# ENTRENADOR_SMD.net
KiCad netlist of a schematic drawn in EAGLE
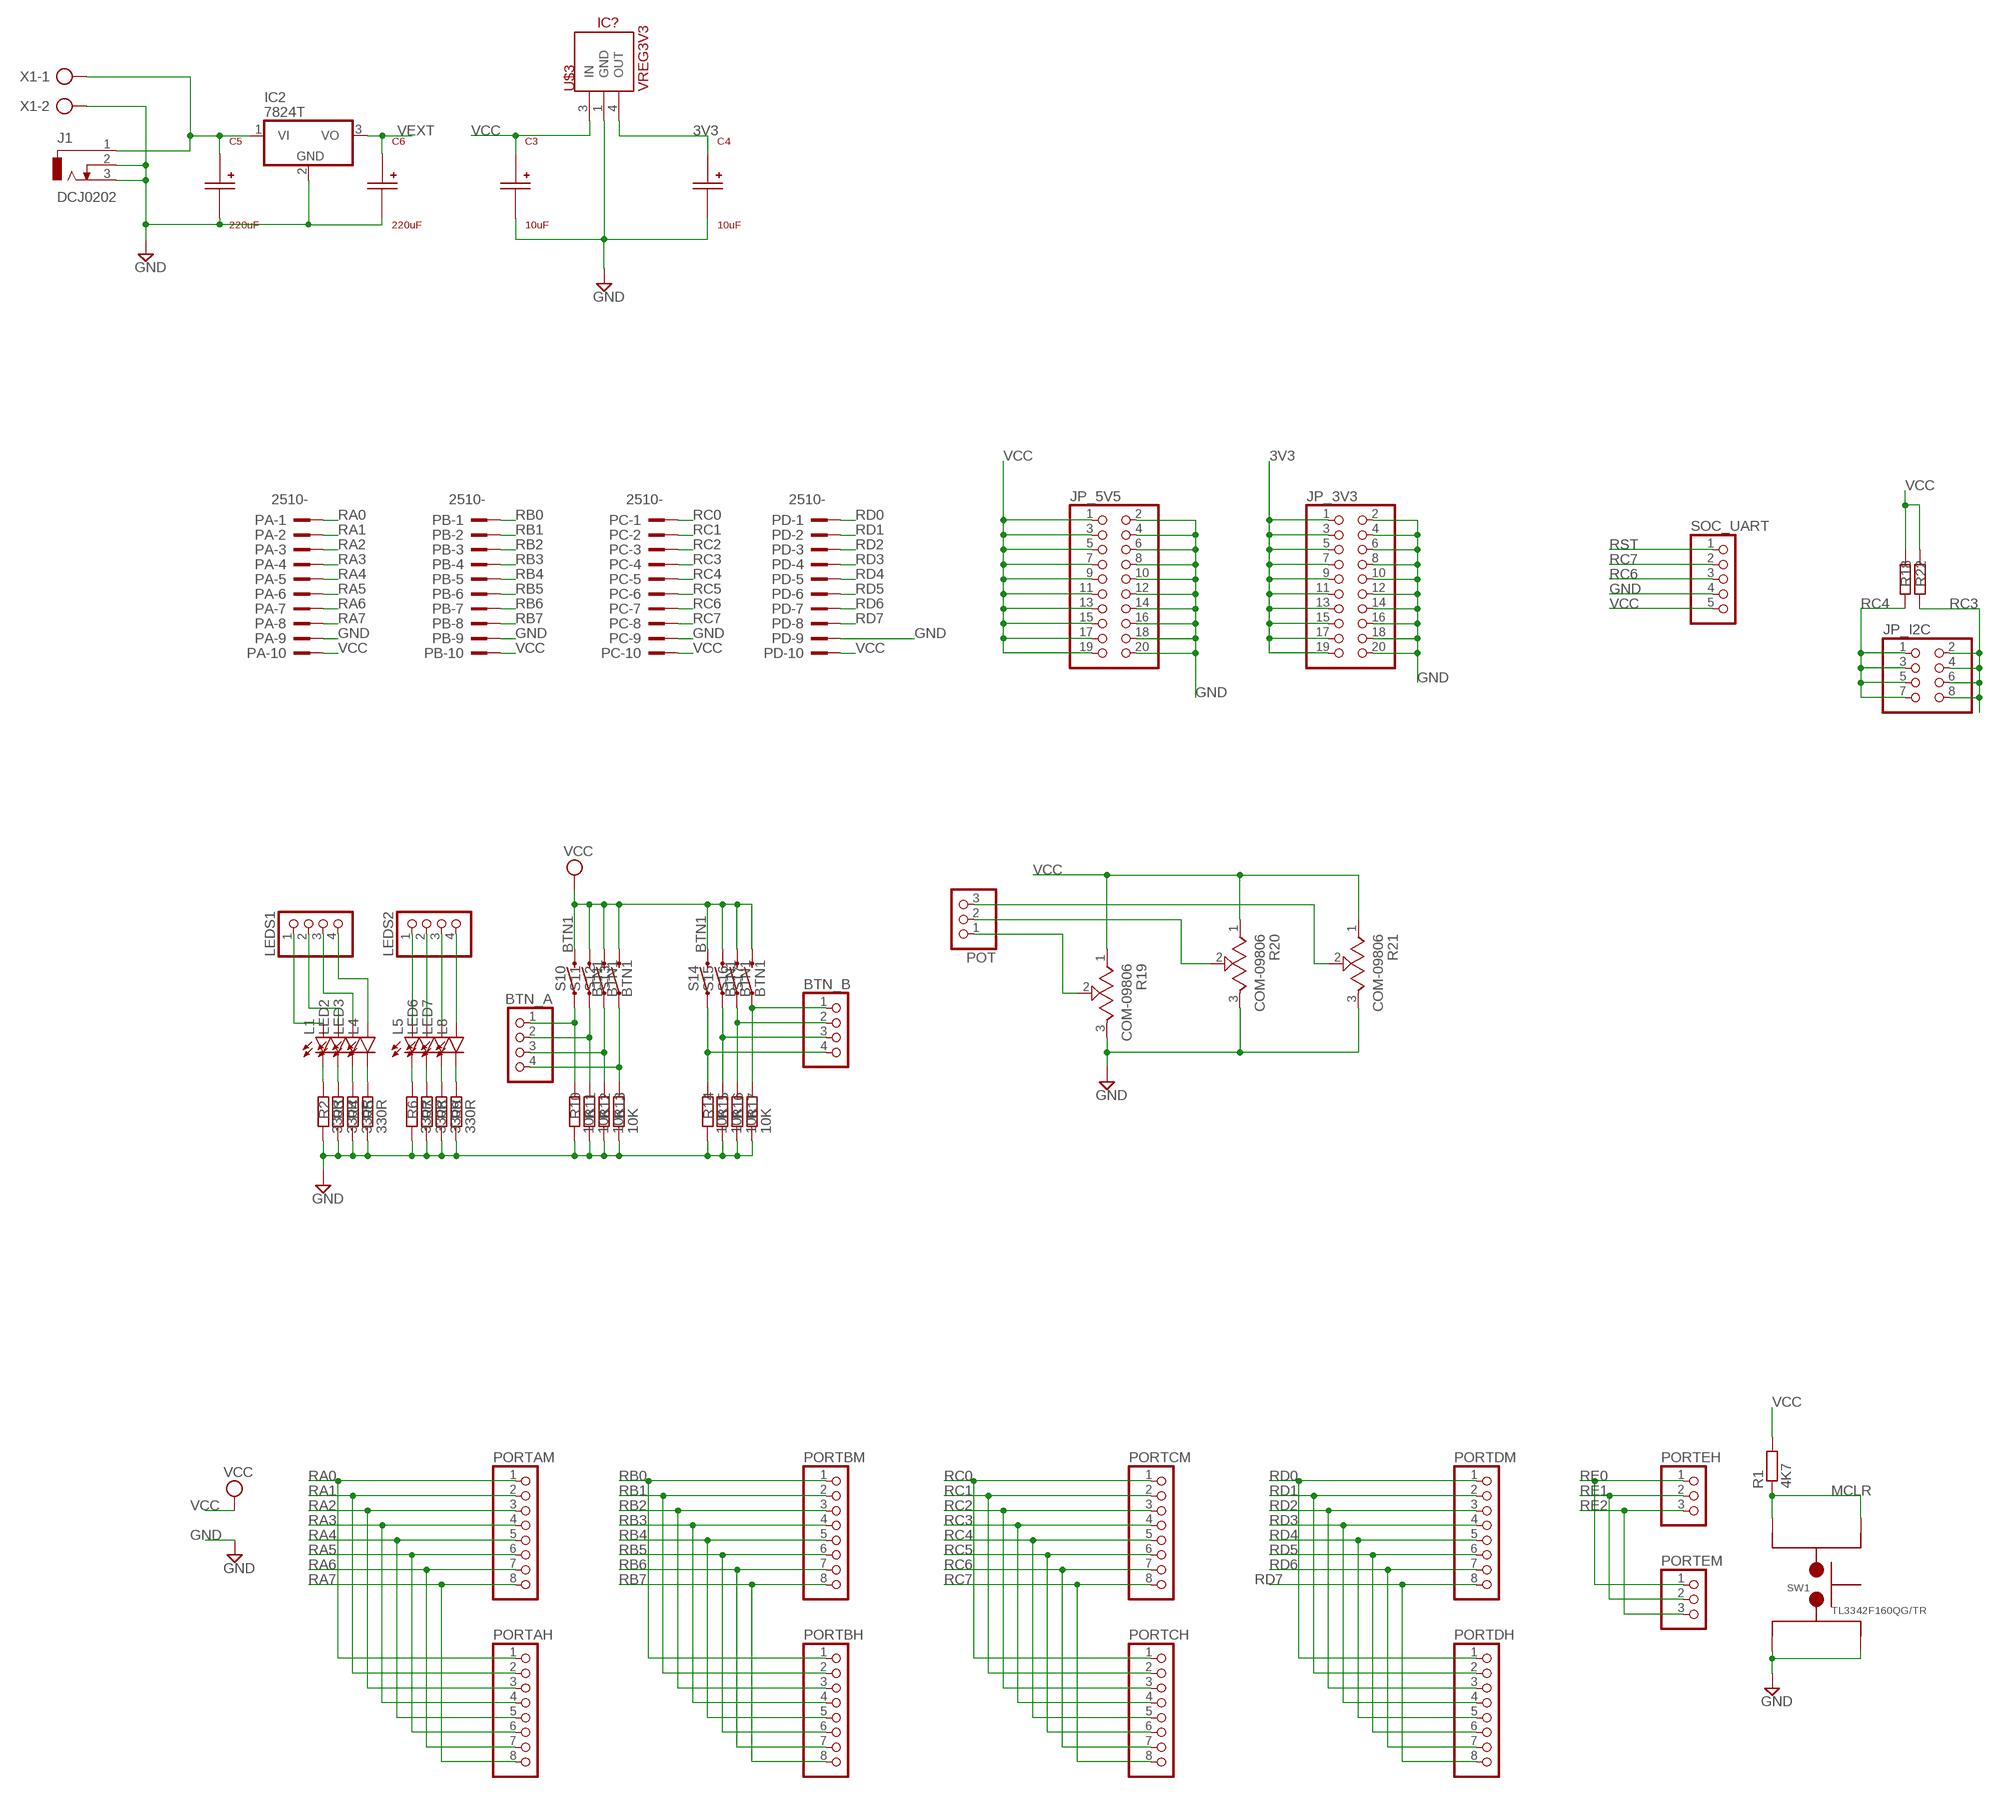
[diagram p0: schematic, sheet 1, part 1 of 2]
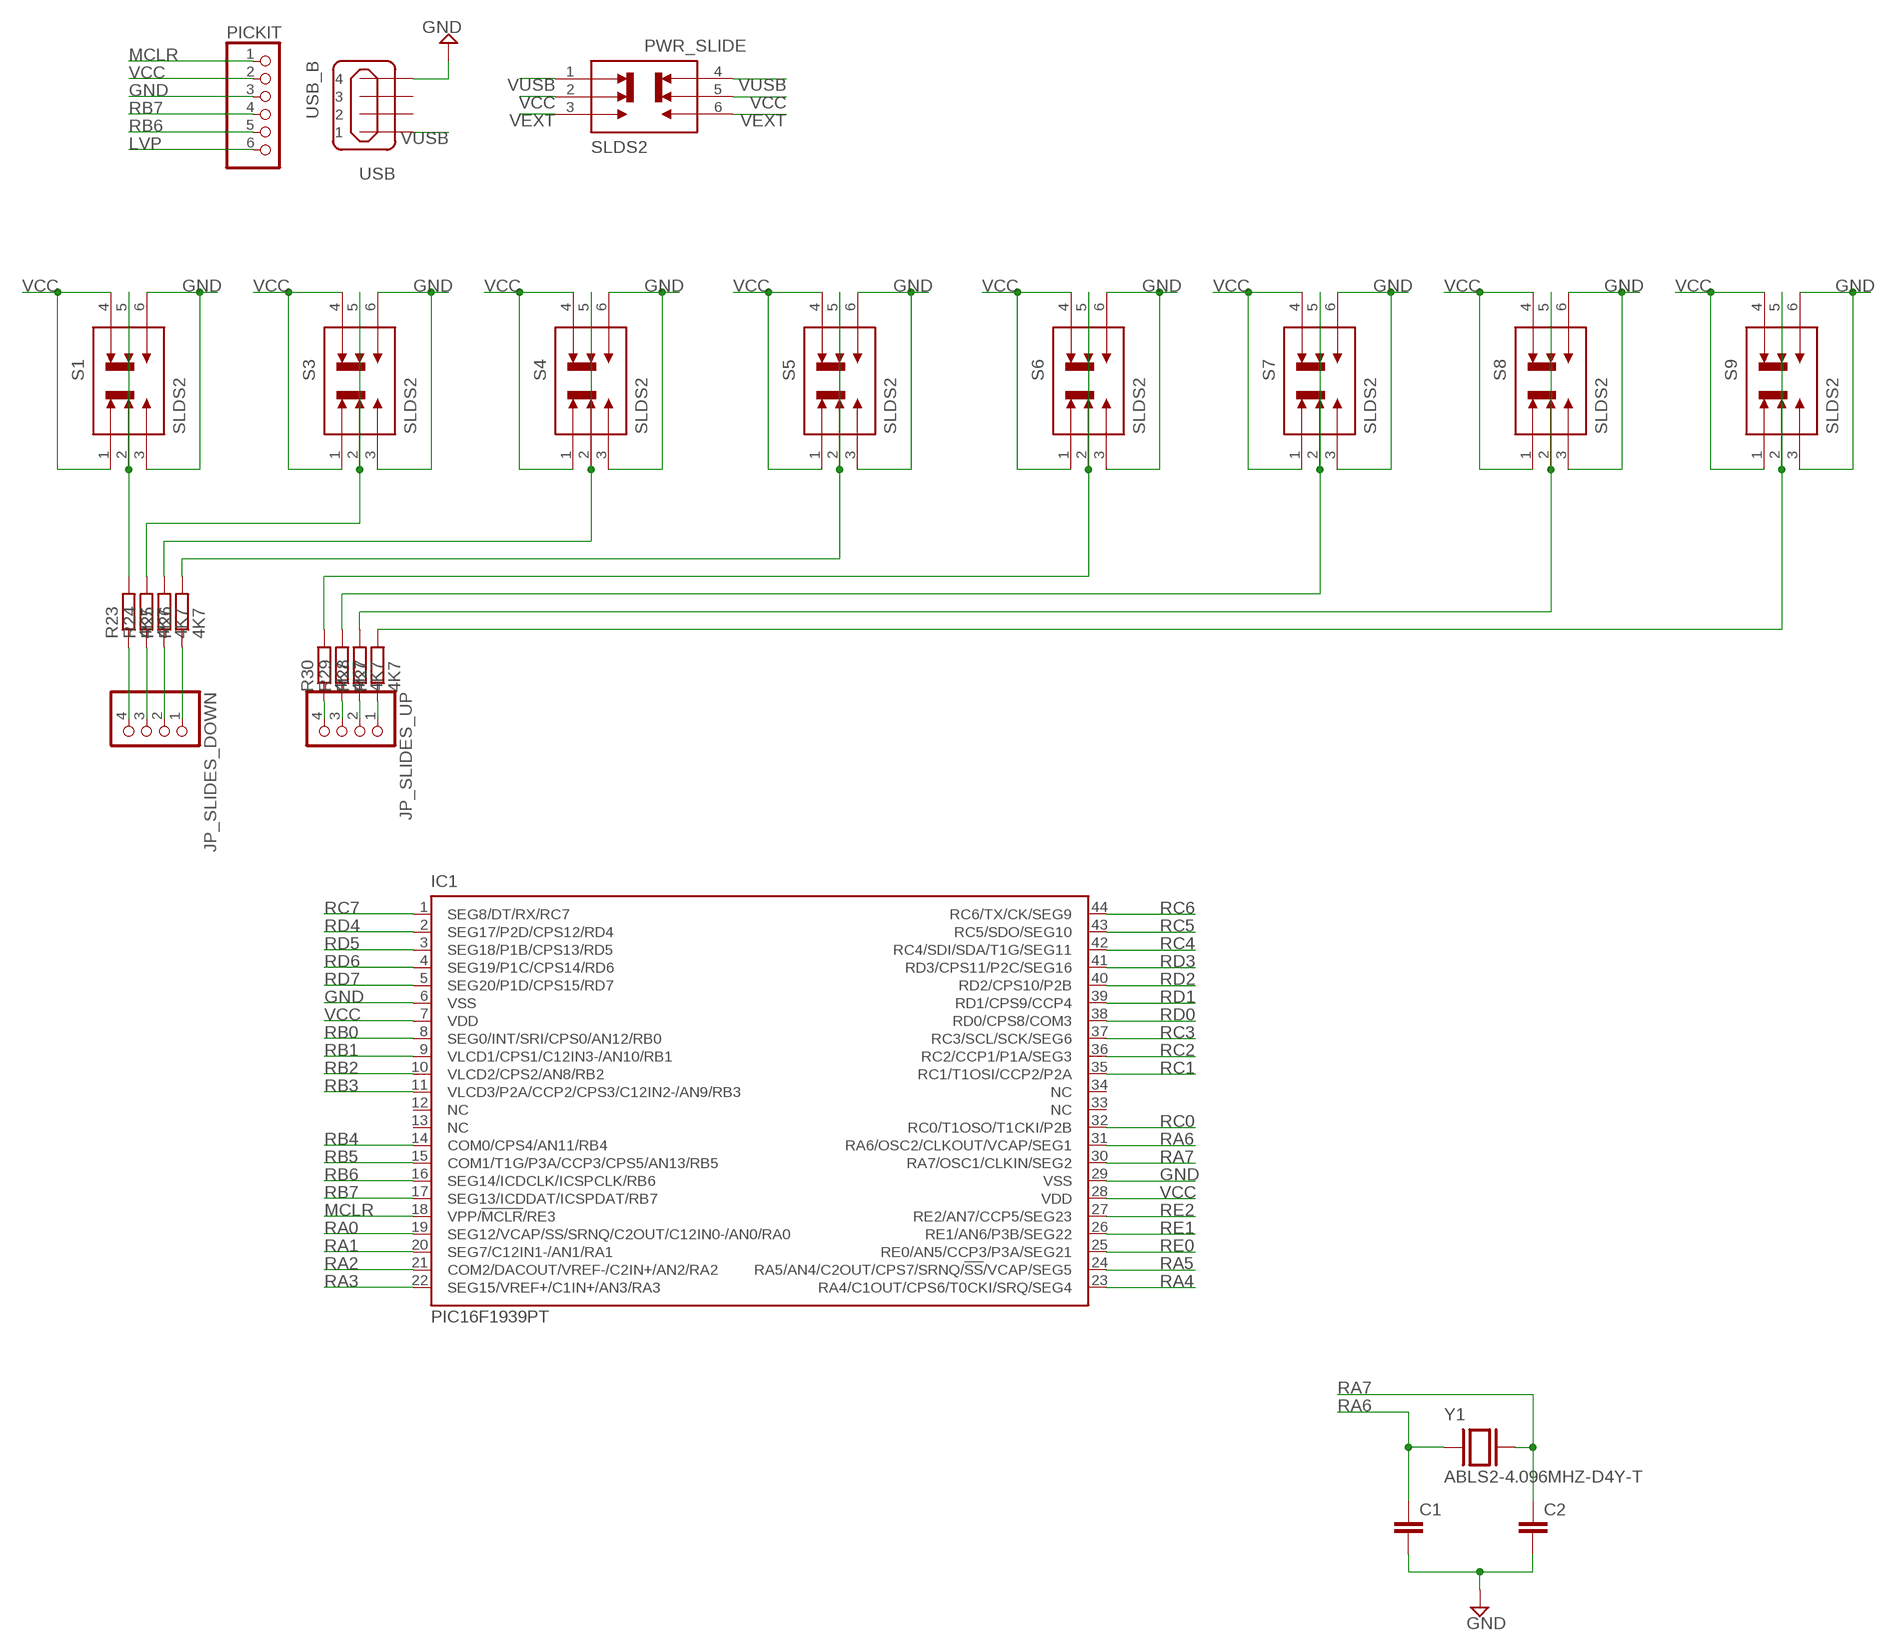
[diagram p1: schematic, sheet 1, part 2 of 2]

(export (version "E")
  (design (tool "Eeschema 10.0.6"))
  (components
    (comp (ref "BTN_A")
      (value "PINHD-1X4")
      (footprint "eagle-import:1X04")
      (libsource (lib "eagle-import") (part "PINHD-1X4"))
    )
    (comp (ref "BTN_B")
      (value "PINHD-1X4")
      (footprint "eagle-import:1X04")
      (libsource (lib "eagle-import") (part "PINHD-1X4"))
    )
    (comp (ref "C1")
      (value "C-EUC0805K")
      (footprint "eagle-import:C0805K")
      (libsource (lib "eagle-import") (part "C-EUC0805K"))
    )
    (comp (ref "C2")
      (value "C-EUC0805K")
      (footprint "eagle-import:C0805K")
      (libsource (lib "eagle-import") (part "C-EUC0805K"))
    )
    (comp (ref "C3")
      (value "10uF")
      (footprint "eagle-import:CAPA")
      (libsource (lib "eagle-import") (part "CAPA"))
    )
    (comp (ref "C4")
      (value "10uF")
      (footprint "eagle-import:CAPA")
      (libsource (lib "eagle-import") (part "CAPA"))
    )
    (comp (ref "C5")
      (value "220uF")
      (footprint "eagle-import:CAPA")
      (libsource (lib "eagle-import") (part "CAPA"))
    )
    (comp (ref "C6")
      (value "220uF")
      (footprint "eagle-import:CAPA")
      (libsource (lib "eagle-import") (part "CAPA"))
    )
    (comp (ref "IC1")
      (value "PIC16F1939PT")
      (footprint "eagle-import:TQFP44")
      (fields (field (name "MPN") "PIC16F1939-I/PT"))
      (libsource (lib "eagle-import") (part "PIC16F193PT9"))
    )
    (comp (ref "IC2")
      (value "7824T")
      (footprint "eagle-import:TO220H")
      (libsource (lib "eagle-import") (part "78T24"))
    )
    (comp (ref "J1")
      (value "DCJ0202")
      (footprint "eagle-import:DCJ0202")
      (libsource (lib "eagle-import") (part "DCJ0202"))
    )
    (comp (ref "JP_3V3")
      (value "PINHD-2X10")
      (footprint "eagle-import:2X10")
      (libsource (lib "eagle-import") (part "PINHD-2X10"))
    )
    (comp (ref "JP_5V5")
      (value "PINHD-2X10")
      (footprint "eagle-import:2X10")
      (libsource (lib "eagle-import") (part "PINHD-2X10"))
    )
    (comp (ref "JP_I2C")
      (value "PINHD-2X4")
      (footprint "eagle-import:2X04")
      (libsource (lib "eagle-import") (part "PINHD-2X4"))
    )
    (comp (ref "JP_SLIDES_DOWN")
      (value "PINHD-1X4")
      (footprint "eagle-import:1X04")
      (libsource (lib "eagle-import") (part "PINHD-1X4"))
    )
    (comp (ref "JP_SLIDES_UP")
      (value "PINHD-1X4")
      (footprint "eagle-import:1X04")
      (libsource (lib "eagle-import") (part "PINHD-1X4"))
    )
    (comp (ref "L1")
      (value "LEDCHIP-LED0805")
      (footprint "eagle-import:CHIP-LED0805")
      (libsource (lib "eagle-import") (part "LEDCHIP-LED0805"))
    )
    (comp (ref "L4")
      (value "LEDCHIP-LED0805")
      (footprint "eagle-import:CHIP-LED0805")
      (libsource (lib "eagle-import") (part "LEDCHIP-LED0805"))
    )
    (comp (ref "L5")
      (value "LEDCHIP-LED0805")
      (footprint "eagle-import:CHIP-LED0805")
      (libsource (lib "eagle-import") (part "LEDCHIP-LED0805"))
    )
    (comp (ref "L8")
      (value "LEDCHIP-LED0805")
      (footprint "eagle-import:CHIP-LED0805")
      (libsource (lib "eagle-import") (part "LEDCHIP-LED0805"))
    )
    (comp (ref "LED2")
      (value "LEDCHIP-LED0805")
      (footprint "eagle-import:CHIP-LED0805")
      (libsource (lib "eagle-import") (part "LEDCHIP-LED0805"))
    )
    (comp (ref "LED3")
      (value "LEDCHIP-LED0805")
      (footprint "eagle-import:CHIP-LED0805")
      (libsource (lib "eagle-import") (part "LEDCHIP-LED0805"))
    )
    (comp (ref "LED6")
      (value "LEDCHIP-LED0805")
      (footprint "eagle-import:CHIP-LED0805")
      (libsource (lib "eagle-import") (part "LEDCHIP-LED0805"))
    )
    (comp (ref "LED7")
      (value "LEDCHIP-LED0805")
      (footprint "eagle-import:CHIP-LED0805")
      (libsource (lib "eagle-import") (part "LEDCHIP-LED0805"))
    )
    (comp (ref "LEDS1")
      (value "PINHD-1X4")
      (footprint "eagle-import:1X04")
      (libsource (lib "eagle-import") (part "PINHD-1X4"))
    )
    (comp (ref "LEDS2")
      (value "PINHD-1X4")
      (footprint "eagle-import:1X04")
      (libsource (lib "eagle-import") (part "PINHD-1X4"))
    )
    (comp (ref "PA")
      (value "2510-")
      (footprint "eagle-import:PAK100_2500-10")
      (fields (field (name "MF") "3M") (field (name "MPN") "2510-6002UB"))
      (libsource (lib "eagle-import") (part "2510-"))
    )
    (comp (ref "PB")
      (value "2510-")
      (footprint "eagle-import:PAK100_2500-10")
      (fields (field (name "MF") "3M") (field (name "MPN") "2510-6002UB"))
      (libsource (lib "eagle-import") (part "2510-"))
    )
    (comp (ref "PC")
      (value "2510-")
      (footprint "eagle-import:PAK100_2500-10")
      (fields (field (name "MF") "3M") (field (name "MPN") "2510-6002UB"))
      (libsource (lib "eagle-import") (part "2510-"))
    )
    (comp (ref "PD")
      (value "2510-")
      (footprint "eagle-import:PAK100_2500-10")
      (fields (field (name "MF") "3M") (field (name "MPN") "2510-6002UB"))
      (libsource (lib "eagle-import") (part "2510-"))
    )
    (comp (ref "PICKIT")
      (value "PINHD-1X6")
      (footprint "eagle-import:1X06")
      (libsource (lib "eagle-import") (part "PINHD-1X6"))
    )
    (comp (ref "PORTAH")
      (value "PINHD-1X8")
      (footprint "eagle-import:1X08")
      (libsource (lib "eagle-import") (part "PINHD-1X8"))
    )
    (comp (ref "PORTAM")
      (value "PINHD-1X8")
      (footprint "eagle-import:1X08")
      (libsource (lib "eagle-import") (part "PINHD-1X8"))
    )
    (comp (ref "PORTBH")
      (value "PINHD-1X8")
      (footprint "eagle-import:1X08")
      (libsource (lib "eagle-import") (part "PINHD-1X8"))
    )
    (comp (ref "PORTBM")
      (value "PINHD-1X8")
      (footprint "eagle-import:1X08")
      (libsource (lib "eagle-import") (part "PINHD-1X8"))
    )
    (comp (ref "PORTCH")
      (value "PINHD-1X8")
      (footprint "eagle-import:1X08")
      (libsource (lib "eagle-import") (part "PINHD-1X8"))
    )
    (comp (ref "PORTCM")
      (value "PINHD-1X8")
      (footprint "eagle-import:1X08")
      (libsource (lib "eagle-import") (part "PINHD-1X8"))
    )
    (comp (ref "PORTDH")
      (value "PINHD-1X8")
      (footprint "eagle-import:1X08")
      (libsource (lib "eagle-import") (part "PINHD-1X8"))
    )
    (comp (ref "PORTDM")
      (value "PINHD-1X8")
      (footprint "eagle-import:1X08")
      (libsource (lib "eagle-import") (part "PINHD-1X8"))
    )
    (comp (ref "PORTEH")
      (value "PINHD-1X3")
      (footprint "eagle-import:1X03")
      (libsource (lib "eagle-import") (part "PINHD-1X3"))
    )
    (comp (ref "PORTEM")
      (value "PINHD-1X3")
      (footprint "eagle-import:1X03")
      (libsource (lib "eagle-import") (part "PINHD-1X3"))
    )
    (comp (ref "POT")
      (value "PINHD-1X3")
      (footprint "eagle-import:1X03")
      (libsource (lib "eagle-import") (part "PINHD-1X3"))
    )
    (comp (ref "PWR_SLIDE")
      (value "SLDS2")
      (footprint "eagle-import:SW_JS202011SCQN")
      (fields (field (name "MF") "C&K") (field (name "MP") "JS202011SCQN"))
      (libsource (lib "eagle-import") (part "JS202011SCQN"))
    )
    (comp (ref "R1")
      (value "4K7")
      (footprint "eagle-import:R0805")
      (libsource (lib "eagle-import") (part "R-EU_R0805"))
    )
    (comp (ref "R2")
      (value "330R")
      (footprint "eagle-import:R0805")
      (libsource (lib "eagle-import") (part "R-EU_R0805"))
    )
    (comp (ref "R3")
      (value "330R")
      (footprint "eagle-import:R0805")
      (libsource (lib "eagle-import") (part "R-EU_R0805"))
    )
    (comp (ref "R4")
      (value "330R")
      (footprint "eagle-import:R0805")
      (libsource (lib "eagle-import") (part "R-EU_R0805"))
    )
    (comp (ref "R5")
      (value "330R")
      (footprint "eagle-import:R0805")
      (libsource (lib "eagle-import") (part "R-EU_R0805"))
    )
    (comp (ref "R6")
      (value "330R")
      (footprint "eagle-import:R0805")
      (libsource (lib "eagle-import") (part "R-EU_R0805"))
    )
    (comp (ref "R7")
      (value "330R")
      (footprint "eagle-import:R0805")
      (libsource (lib "eagle-import") (part "R-EU_R0805"))
    )
    (comp (ref "R8")
      (value "330R")
      (footprint "eagle-import:R0805")
      (libsource (lib "eagle-import") (part "R-EU_R0805"))
    )
    (comp (ref "R9")
      (value "330R")
      (footprint "eagle-import:R0805")
      (libsource (lib "eagle-import") (part "R-EU_R0805"))
    )
    (comp (ref "R10")
      (value "10K")
      (footprint "eagle-import:R0805")
      (libsource (lib "eagle-import") (part "R-EU_R0805"))
    )
    (comp (ref "R11")
      (value "10K")
      (footprint "eagle-import:R0805")
      (libsource (lib "eagle-import") (part "R-EU_R0805"))
    )
    (comp (ref "R12")
      (value "10K")
      (footprint "eagle-import:R0805")
      (libsource (lib "eagle-import") (part "R-EU_R0805"))
    )
    (comp (ref "R13")
      (value "10K")
      (footprint "eagle-import:R0805")
      (libsource (lib "eagle-import") (part "R-EU_R0805"))
    )
    (comp (ref "R14")
      (value "10K")
      (footprint "eagle-import:R0805")
      (libsource (lib "eagle-import") (part "R-EU_R0805"))
    )
    (comp (ref "R15")
      (value "10K")
      (footprint "eagle-import:R0805")
      (libsource (lib "eagle-import") (part "R-EU_R0805"))
    )
    (comp (ref "R16")
      (value "10K")
      (footprint "eagle-import:R0805")
      (libsource (lib "eagle-import") (part "R-EU_R0805"))
    )
    (comp (ref "R17")
      (value "10K")
      (footprint "eagle-import:R0805")
      (libsource (lib "eagle-import") (part "R-EU_R0805"))
    )
    (comp (ref "R18")
      (value "R-EU_R0805")
      (footprint "eagle-import:R0805")
      (libsource (lib "eagle-import") (part "R-EU_R0805"))
    )
    (comp (ref "R19")
      (value "COM-09806")
      (footprint "eagle-import:TRIM_COM-09806")
      (fields (field (name "MF") "SparkFun Electronics"))
      (libsource (lib "eagle-import") (part "COM-09806"))
    )
    (comp (ref "R20")
      (value "COM-09806")
      (footprint "eagle-import:TRIM_COM-09806")
      (fields (field (name "MF") "SparkFun Electronics"))
      (libsource (lib "eagle-import") (part "COM-09806"))
    )
    (comp (ref "R21")
      (value "COM-09806")
      (footprint "eagle-import:TRIM_COM-09806")
      (fields (field (name "MF") "SparkFun Electronics"))
      (libsource (lib "eagle-import") (part "COM-09806"))
    )
    (comp (ref "R22")
      (value "R-EU_R0805")
      (footprint "eagle-import:R0805")
      (libsource (lib "eagle-import") (part "R-EU_R0805"))
    )
    (comp (ref "R23")
      (value "4K7")
      (footprint "eagle-import:R0805")
      (libsource (lib "eagle-import") (part "R-EU_R0805"))
    )
    (comp (ref "R24")
      (value "4K7")
      (footprint "eagle-import:R0805")
      (libsource (lib "eagle-import") (part "R-EU_R0805"))
    )
    (comp (ref "R25")
      (value "4K7")
      (footprint "eagle-import:R0805")
      (libsource (lib "eagle-import") (part "R-EU_R0805"))
    )
    (comp (ref "R26")
      (value "4K7")
      (footprint "eagle-import:R0805")
      (libsource (lib "eagle-import") (part "R-EU_R0805"))
    )
    (comp (ref "R27")
      (value "4K7")
      (footprint "eagle-import:R0805")
      (libsource (lib "eagle-import") (part "R-EU_R0805"))
    )
    (comp (ref "R28")
      (value "4K7")
      (footprint "eagle-import:R0805")
      (libsource (lib "eagle-import") (part "R-EU_R0805"))
    )
    (comp (ref "R29")
      (value "4K7")
      (footprint "eagle-import:R0805")
      (libsource (lib "eagle-import") (part "R-EU_R0805"))
    )
    (comp (ref "R30")
      (value "4K7")
      (footprint "eagle-import:R0805")
      (libsource (lib "eagle-import") (part "R-EU_R0805"))
    )
    (comp (ref "S1")
      (value "SLDS2")
      (footprint "eagle-import:SW_JS202011SCQN")
      (fields (field (name "MF") "C&K") (field (name "MP") "JS202011SCQN"))
      (libsource (lib "eagle-import") (part "JS202011SCQN"))
    )
    (comp (ref "S3")
      (value "SLDS2")
      (footprint "eagle-import:SW_JS202011SCQN")
      (fields (field (name "MF") "C&K") (field (name "MP") "JS202011SCQN"))
      (libsource (lib "eagle-import") (part "JS202011SCQN"))
    )
    (comp (ref "S4")
      (value "SLDS2")
      (footprint "eagle-import:SW_JS202011SCQN")
      (fields (field (name "MF") "C&K") (field (name "MP") "JS202011SCQN"))
      (libsource (lib "eagle-import") (part "JS202011SCQN"))
    )
    (comp (ref "S5")
      (value "SLDS2")
      (footprint "eagle-import:SW_JS202011SCQN")
      (fields (field (name "MF") "C&K") (field (name "MP") "JS202011SCQN"))
      (libsource (lib "eagle-import") (part "JS202011SCQN"))
    )
    (comp (ref "S6")
      (value "SLDS2")
      (footprint "eagle-import:SW_JS202011SCQN")
      (fields (field (name "MF") "C&K") (field (name "MP") "JS202011SCQN"))
      (libsource (lib "eagle-import") (part "JS202011SCQN"))
    )
    (comp (ref "S7")
      (value "SLDS2")
      (footprint "eagle-import:SW_JS202011SCQN")
      (fields (field (name "MF") "C&K") (field (name "MP") "JS202011SCQN"))
      (libsource (lib "eagle-import") (part "JS202011SCQN"))
    )
    (comp (ref "S8")
      (value "SLDS2")
      (footprint "eagle-import:SW_JS202011SCQN")
      (fields (field (name "MF") "C&K") (field (name "MP") "JS202011SCQN"))
      (libsource (lib "eagle-import") (part "JS202011SCQN"))
    )
    (comp (ref "S9")
      (value "SLDS2")
      (footprint "eagle-import:SW_JS202011SCQN")
      (fields (field (name "MF") "C&K") (field (name "MP") "JS202011SCQN"))
      (libsource (lib "eagle-import") (part "JS202011SCQN"))
    )
    (comp (ref "S10")
      (value "BTN1")
      (footprint "eagle-import:TACTILE_SWITCH_SMD_6.0X3.5MM")
      (fields (field (name "MF") "CK") (field (name "MP") "PTS636SM25FSMTRLFS"))
      (libsource (lib "eagle-import") (part "PTS636SM25FSMTRLFS-SMD-6.0X3.5MM"))
    )
    (comp (ref "S11")
      (value "BTN1")
      (footprint "eagle-import:TACTILE_SWITCH_SMD_6.0X3.5MM")
      (fields (field (name "MF") "CK") (field (name "MP") "PTS636SM25FSMTRLFS"))
      (libsource (lib "eagle-import") (part "PTS636SM25FSMTRLFS-SMD-6.0X3.5MM"))
    )
    (comp (ref "S12")
      (value "BTN1")
      (footprint "eagle-import:TACTILE_SWITCH_SMD_6.0X3.5MM")
      (fields (field (name "MF") "CK") (field (name "MP") "PTS636SM25FSMTRLFS"))
      (libsource (lib "eagle-import") (part "PTS636SM25FSMTRLFS-SMD-6.0X3.5MM"))
    )
    (comp (ref "S13")
      (value "BTN1")
      (footprint "eagle-import:TACTILE_SWITCH_SMD_6.0X3.5MM")
      (fields (field (name "MF") "CK") (field (name "MP") "PTS636SM25FSMTRLFS"))
      (libsource (lib "eagle-import") (part "PTS636SM25FSMTRLFS-SMD-6.0X3.5MM"))
    )
    (comp (ref "S14")
      (value "BTN1")
      (footprint "eagle-import:TACTILE_SWITCH_SMD_6.0X3.5MM")
      (fields (field (name "MF") "CK") (field (name "MP") "PTS636SM25FSMTRLFS"))
      (libsource (lib "eagle-import") (part "PTS636SM25FSMTRLFS-SMD-6.0X3.5MM"))
    )
    (comp (ref "S15")
      (value "BTN1")
      (footprint "eagle-import:TACTILE_SWITCH_SMD_6.0X3.5MM")
      (fields (field (name "MF") "CK") (field (name "MP") "PTS636SM25FSMTRLFS"))
      (libsource (lib "eagle-import") (part "PTS636SM25FSMTRLFS-SMD-6.0X3.5MM"))
    )
    (comp (ref "S16")
      (value "BTN1")
      (footprint "eagle-import:TACTILE_SWITCH_SMD_6.0X3.5MM")
      (fields (field (name "MF") "CK") (field (name "MP") "PTS636SM25FSMTRLFS"))
      (libsource (lib "eagle-import") (part "PTS636SM25FSMTRLFS-SMD-6.0X3.5MM"))
    )
    (comp (ref "S17")
      (value "BTN1")
      (footprint "eagle-import:TACTILE_SWITCH_SMD_6.0X3.5MM")
      (fields (field (name "MF") "CK") (field (name "MP") "PTS636SM25FSMTRLFS"))
      (libsource (lib "eagle-import") (part "PTS636SM25FSMTRLFS-SMD-6.0X3.5MM"))
    )
    (comp (ref "SOC_UART")
      (value "PINHD-1X5")
      (footprint "eagle-import:1X05")
      (libsource (lib "eagle-import") (part "PINHD-1X5"))
    )
    (comp (ref "SW1")
      (value "TL3342F160QG/TR")
      (footprint "eagle-import:SW_TL3342F160QG_TR")
      (fields (field (name "MF") "E-Switch"))
      (libsource (lib "eagle-import") (part "TL3342F160QG/TR"))
    )
    (comp (ref "U$3")
      (value "VREG3V3")
      (footprint "eagle-import:VREG3V3")
      (libsource (lib "eagle-import") (part "VREG3V3"))
    )
    (comp (ref "USB")
      (value "USB_B")
      (footprint "eagle-import:85-32004-10X")
      (libsource (lib "eagle-import") (part "MINI-USB_4P-85-32004-10X"))
    )
    (comp (ref "X1")
      (value "AK300/2")
      (footprint "eagle-import:AK300_2")
      (libsource (lib "eagle-import") (part "AK300/2"))
    )
    (comp (ref "Y1")
      (value "ABLS2-4.096MHZ-D4Y-T")
      (footprint "eagle-import:XTAL_ABLS2-4.096MHZ-D4Y-T")
      (fields (field (name "MF") "Abracon LLC"))
      (libsource (lib "eagle-import") (part "ABLS2-4.096MHZ-D4Y-T"))
    )
  )
  (nets
    (net (code "1") (name "/3V3") (class "Default")
      (node (ref "C4") (pin "P") (pinfunction "P_P") (pintype "bidirectional"))
      (node (ref "JP_3V3") (pin "1") (pinfunction "1_1") (pintype "passive"))
      (node (ref "JP_3V3") (pin "11") (pinfunction "11_11") (pintype "passive"))
      (node (ref "JP_3V3") (pin "13") (pinfunction "13_13") (pintype "passive"))
      (node (ref "JP_3V3") (pin "15") (pinfunction "15_15") (pintype "passive"))
      (node (ref "JP_3V3") (pin "17") (pinfunction "17_17") (pintype "passive"))
      (node (ref "JP_3V3") (pin "19") (pinfunction "19_19") (pintype "passive"))
      (node (ref "JP_3V3") (pin "3") (pinfunction "3_3") (pintype "passive"))
      (node (ref "JP_3V3") (pin "5") (pinfunction "5_5") (pintype "passive"))
      (node (ref "JP_3V3") (pin "7") (pinfunction "7_7") (pintype "passive"))
      (node (ref "JP_3V3") (pin "9") (pinfunction "9_9") (pintype "passive"))
      (node (ref "U$3") (pin "4") (pinfunction "OUT_4") (pintype "bidirectional"))
    )
    (net (code "2") (name "/LVP") (class "Default")
      (node (ref "PICKIT") (pin "6") (pinfunction "6_6") (pintype "passive"))
    )
    (net (code "3") (name "/MCLR") (class "Default")
      (node (ref "IC1") (pin "18") (pinfunction "VPP/~{MCLR}/RE3_18") (pintype "input"))
      (node (ref "PICKIT") (pin "1") (pinfunction "1_1") (pintype "passive"))
      (node (ref "R1") (pin "1") (pinfunction "1_1") (pintype "passive"))
      (node (ref "SW1") (pin "3") (pinfunction "3_3") (pintype "passive"))
      (node (ref "SW1") (pin "4") (pinfunction "4_4") (pintype "passive"))
    )
    (net (code "4") (name "/RA0") (class "Default")
      (node (ref "IC1") (pin "19") (pinfunction "SEG12/VCAP/SS/SRNQ/C2OUT/C12IN0-/AN0/RA0_19") (pintype "bidirectional"))
      (node (ref "PA") (pin "1") (pinfunction "KL_1") (pintype "passive"))
      (node (ref "PORTAH") (pin "1") (pinfunction "1_1") (pintype "passive"))
      (node (ref "PORTAM") (pin "1") (pinfunction "1_1") (pintype "passive"))
    )
    (net (code "5") (name "/RA1") (class "Default")
      (node (ref "IC1") (pin "20") (pinfunction "SEG7/C12IN1-/AN1/RA1_20") (pintype "bidirectional"))
      (node (ref "PA") (pin "2") (pinfunction "KL_2") (pintype "passive"))
      (node (ref "PORTAH") (pin "2") (pinfunction "2_2") (pintype "passive"))
      (node (ref "PORTAM") (pin "2") (pinfunction "2_2") (pintype "passive"))
    )
    (net (code "6") (name "/RA2") (class "Default")
      (node (ref "IC1") (pin "21") (pinfunction "COM2/DACOUT/VREF-/C2IN+/AN2/RA2_21") (pintype "bidirectional"))
      (node (ref "PA") (pin "3") (pinfunction "KL_3") (pintype "passive"))
      (node (ref "PORTAH") (pin "3") (pinfunction "3_3") (pintype "passive"))
      (node (ref "PORTAM") (pin "3") (pinfunction "3_3") (pintype "passive"))
    )
    (net (code "7") (name "/RA3") (class "Default")
      (node (ref "IC1") (pin "22") (pinfunction "SEG15/VREF+/C1IN+/AN3/RA3_22") (pintype "bidirectional"))
      (node (ref "PA") (pin "4") (pinfunction "KL_4") (pintype "passive"))
      (node (ref "PORTAH") (pin "4") (pinfunction "4_4") (pintype "passive"))
      (node (ref "PORTAM") (pin "4") (pinfunction "4_4") (pintype "passive"))
    )
    (net (code "8") (name "/RA4") (class "Default")
      (node (ref "IC1") (pin "23") (pinfunction "RA4/C1OUT/CPS6/T0CKI/SRQ/SEG4_23") (pintype "bidirectional"))
      (node (ref "PA") (pin "5") (pinfunction "KL_5") (pintype "passive"))
      (node (ref "PORTAH") (pin "5") (pinfunction "5_5") (pintype "passive"))
      (node (ref "PORTAM") (pin "5") (pinfunction "5_5") (pintype "passive"))
    )
    (net (code "9") (name "/RA5") (class "Default")
      (node (ref "IC1") (pin "24") (pinfunction "RA5/AN4/C2OUT/CPS7/SRNQ/~{SS}/VCAP/SEG5_24") (pintype "bidirectional"))
      (node (ref "PA") (pin "6") (pinfunction "KL_6") (pintype "passive"))
      (node (ref "PORTAH") (pin "6") (pinfunction "6_6") (pintype "passive"))
      (node (ref "PORTAM") (pin "6") (pinfunction "6_6") (pintype "passive"))
    )
    (net (code "10") (name "/RA6") (class "Default")
      (node (ref "C1") (pin "1") (pinfunction "1_1") (pintype "passive"))
      (node (ref "IC1") (pin "31") (pinfunction "RA6/OSC2/CLKOUT/VCAP/SEG1_31") (pintype "bidirectional"))
      (node (ref "PA") (pin "7") (pinfunction "KL_7") (pintype "passive"))
      (node (ref "PORTAH") (pin "7") (pinfunction "7_7") (pintype "passive"))
      (node (ref "PORTAM") (pin "7") (pinfunction "7_7") (pintype "passive"))
      (node (ref "Y1") (pin "1") (pinfunction "1_1") (pintype "passive"))
    )
    (net (code "11") (name "/RA7") (class "Default")
      (node (ref "C2") (pin "1") (pinfunction "1_1") (pintype "passive"))
      (node (ref "IC1") (pin "30") (pinfunction "RA7/OSC1/CLKIN/SEG2_30") (pintype "bidirectional"))
      (node (ref "PA") (pin "8") (pinfunction "KL_8") (pintype "passive"))
      (node (ref "PORTAH") (pin "8") (pinfunction "8_8") (pintype "passive"))
      (node (ref "PORTAM") (pin "8") (pinfunction "8_8") (pintype "passive"))
      (node (ref "Y1") (pin "2") (pinfunction "2_2") (pintype "passive"))
    )
    (net (code "12") (name "/RB0") (class "Default")
      (node (ref "IC1") (pin "8") (pinfunction "SEG0/INT/SRI/CPS0/AN12/RB0_8") (pintype "bidirectional"))
      (node (ref "PB") (pin "1") (pinfunction "KL_1") (pintype "passive"))
      (node (ref "PORTBH") (pin "1") (pinfunction "1_1") (pintype "passive"))
      (node (ref "PORTBM") (pin "1") (pinfunction "1_1") (pintype "passive"))
    )
    (net (code "13") (name "/RB1") (class "Default")
      (node (ref "IC1") (pin "9") (pinfunction "VLCD1/CPS1/C12IN3-/AN10/RB1_9") (pintype "bidirectional"))
      (node (ref "PB") (pin "2") (pinfunction "KL_2") (pintype "passive"))
      (node (ref "PORTBH") (pin "2") (pinfunction "2_2") (pintype "passive"))
      (node (ref "PORTBM") (pin "2") (pinfunction "2_2") (pintype "passive"))
    )
    (net (code "14") (name "/RB2") (class "Default")
      (node (ref "IC1") (pin "10") (pinfunction "VLCD2/CPS2/AN8/RB2_10") (pintype "bidirectional"))
      (node (ref "PB") (pin "3") (pinfunction "KL_3") (pintype "passive"))
      (node (ref "PORTBH") (pin "3") (pinfunction "3_3") (pintype "passive"))
      (node (ref "PORTBM") (pin "3") (pinfunction "3_3") (pintype "passive"))
    )
    (net (code "15") (name "/RB3") (class "Default")
      (node (ref "IC1") (pin "11") (pinfunction "VLCD3/P2A/CCP2/CPS3/C12IN2-/AN9/RB3_11") (pintype "bidirectional"))
      (node (ref "PB") (pin "4") (pinfunction "KL_4") (pintype "passive"))
      (node (ref "PORTBH") (pin "4") (pinfunction "4_4") (pintype "passive"))
      (node (ref "PORTBM") (pin "4") (pinfunction "4_4") (pintype "passive"))
    )
    (net (code "16") (name "/RB4") (class "Default")
      (node (ref "IC1") (pin "14") (pinfunction "COM0/CPS4/AN11/RB4_14") (pintype "bidirectional"))
      (node (ref "PB") (pin "5") (pinfunction "KL_5") (pintype "passive"))
      (node (ref "PORTBH") (pin "5") (pinfunction "5_5") (pintype "passive"))
      (node (ref "PORTBM") (pin "5") (pinfunction "5_5") (pintype "passive"))
    )
    (net (code "17") (name "/RB5") (class "Default")
      (node (ref "IC1") (pin "15") (pinfunction "COM1/T1G/P3A/CCP3/CPS5/AN13/RB5_15") (pintype "bidirectional"))
      (node (ref "PB") (pin "6") (pinfunction "KL_6") (pintype "passive"))
      (node (ref "PORTBH") (pin "6") (pinfunction "6_6") (pintype "passive"))
      (node (ref "PORTBM") (pin "6") (pinfunction "6_6") (pintype "passive"))
    )
    (net (code "18") (name "/RB6") (class "Default")
      (node (ref "IC1") (pin "16") (pinfunction "SEG14/ICDCLK/ICSPCLK/RB6_16") (pintype "bidirectional"))
      (node (ref "PB") (pin "7") (pinfunction "KL_7") (pintype "passive"))
      (node (ref "PICKIT") (pin "5") (pinfunction "5_5") (pintype "passive"))
      (node (ref "PORTBH") (pin "7") (pinfunction "7_7") (pintype "passive"))
      (node (ref "PORTBM") (pin "7") (pinfunction "7_7") (pintype "passive"))
    )
    (net (code "19") (name "/RB7") (class "Default")
      (node (ref "IC1") (pin "17") (pinfunction "SEG13/ICDDAT/ICSPDAT/RB7_17") (pintype "bidirectional"))
      (node (ref "PB") (pin "8") (pinfunction "KL_8") (pintype "passive"))
      (node (ref "PICKIT") (pin "4") (pinfunction "4_4") (pintype "passive"))
      (node (ref "PORTBH") (pin "8") (pinfunction "8_8") (pintype "passive"))
      (node (ref "PORTBM") (pin "8") (pinfunction "8_8") (pintype "passive"))
    )
    (net (code "20") (name "/RC0") (class "Default")
      (node (ref "IC1") (pin "32") (pinfunction "RC0/T1OSO/T1CKI/P2B_32") (pintype "bidirectional"))
      (node (ref "PC") (pin "1") (pinfunction "KL_1") (pintype "passive"))
      (node (ref "PORTCH") (pin "1") (pinfunction "1_1") (pintype "passive"))
      (node (ref "PORTCM") (pin "1") (pinfunction "1_1") (pintype "passive"))
    )
    (net (code "21") (name "/RC1") (class "Default")
      (node (ref "IC1") (pin "35") (pinfunction "RC1/T1OSI/CCP2/P2A_35") (pintype "bidirectional"))
      (node (ref "PC") (pin "2") (pinfunction "KL_2") (pintype "passive"))
      (node (ref "PORTCH") (pin "2") (pinfunction "2_2") (pintype "passive"))
      (node (ref "PORTCM") (pin "2") (pinfunction "2_2") (pintype "passive"))
    )
    (net (code "22") (name "/RC2") (class "Default")
      (node (ref "IC1") (pin "36") (pinfunction "RC2/CCP1/P1A/SEG3_36") (pintype "bidirectional"))
      (node (ref "PC") (pin "3") (pinfunction "KL_3") (pintype "passive"))
      (node (ref "PORTCH") (pin "3") (pinfunction "3_3") (pintype "passive"))
      (node (ref "PORTCM") (pin "3") (pinfunction "3_3") (pintype "passive"))
    )
    (net (code "23") (name "/RC3") (class "Default")
      (node (ref "IC1") (pin "37") (pinfunction "RC3/SCL/SCK/SEG6_37") (pintype "bidirectional"))
      (node (ref "JP_I2C") (pin "2") (pinfunction "2_2") (pintype "passive"))
      (node (ref "JP_I2C") (pin "4") (pinfunction "4_4") (pintype "passive"))
      (node (ref "JP_I2C") (pin "6") (pinfunction "6_6") (pintype "passive"))
      (node (ref "JP_I2C") (pin "8") (pinfunction "8_8") (pintype "passive"))
      (node (ref "PC") (pin "4") (pinfunction "KL_4") (pintype "passive"))
      (node (ref "PORTCH") (pin "4") (pinfunction "4_4") (pintype "passive"))
      (node (ref "PORTCM") (pin "4") (pinfunction "4_4") (pintype "passive"))
      (node (ref "R22") (pin "1") (pinfunction "1_1") (pintype "passive"))
    )
    (net (code "24") (name "/RC4") (class "Default")
      (node (ref "IC1") (pin "42") (pinfunction "RC4/SDI/SDA/T1G/SEG11_42") (pintype "bidirectional"))
      (node (ref "JP_I2C") (pin "1") (pinfunction "1_1") (pintype "passive"))
      (node (ref "JP_I2C") (pin "3") (pinfunction "3_3") (pintype "passive"))
      (node (ref "JP_I2C") (pin "5") (pinfunction "5_5") (pintype "passive"))
      (node (ref "JP_I2C") (pin "7") (pinfunction "7_7") (pintype "passive"))
      (node (ref "PC") (pin "5") (pinfunction "KL_5") (pintype "passive"))
      (node (ref "PORTCH") (pin "5") (pinfunction "5_5") (pintype "passive"))
      (node (ref "PORTCM") (pin "5") (pinfunction "5_5") (pintype "passive"))
      (node (ref "R18") (pin "1") (pinfunction "1_1") (pintype "passive"))
    )
    (net (code "25") (name "/RC5") (class "Default")
      (node (ref "IC1") (pin "43") (pinfunction "RC5/SDO/SEG10_43") (pintype "bidirectional"))
      (node (ref "PC") (pin "6") (pinfunction "KL_6") (pintype "passive"))
      (node (ref "PORTCH") (pin "6") (pinfunction "6_6") (pintype "passive"))
      (node (ref "PORTCM") (pin "6") (pinfunction "6_6") (pintype "passive"))
    )
    (net (code "26") (name "/RC6") (class "Default")
      (node (ref "IC1") (pin "44") (pinfunction "RC6/TX/CK/SEG9_44") (pintype "bidirectional"))
      (node (ref "PC") (pin "7") (pinfunction "KL_7") (pintype "passive"))
      (node (ref "PORTCH") (pin "7") (pinfunction "7_7") (pintype "passive"))
      (node (ref "PORTCM") (pin "7") (pinfunction "7_7") (pintype "passive"))
      (node (ref "SOC_UART") (pin "3") (pinfunction "3_3") (pintype "passive"))
    )
    (net (code "27") (name "/RC7") (class "Default")
      (node (ref "IC1") (pin "1") (pinfunction "SEG8/DT/RX/RC7_1") (pintype "bidirectional"))
      (node (ref "PC") (pin "8") (pinfunction "KL_8") (pintype "passive"))
      (node (ref "PORTCH") (pin "8") (pinfunction "8_8") (pintype "passive"))
      (node (ref "PORTCM") (pin "8") (pinfunction "8_8") (pintype "passive"))
      (node (ref "SOC_UART") (pin "2") (pinfunction "2_2") (pintype "passive"))
    )
    (net (code "28") (name "/RD0") (class "Default")
      (node (ref "IC1") (pin "38") (pinfunction "RD0/CPS8/COM3_38") (pintype "bidirectional"))
      (node (ref "PD") (pin "1") (pinfunction "KL_1") (pintype "passive"))
      (node (ref "PORTDH") (pin "1") (pinfunction "1_1") (pintype "passive"))
      (node (ref "PORTDM") (pin "1") (pinfunction "1_1") (pintype "passive"))
    )
    (net (code "29") (name "/RD1") (class "Default")
      (node (ref "IC1") (pin "39") (pinfunction "RD1/CPS9/CCP4_39") (pintype "bidirectional"))
      (node (ref "PD") (pin "2") (pinfunction "KL_2") (pintype "passive"))
      (node (ref "PORTDH") (pin "2") (pinfunction "2_2") (pintype "passive"))
      (node (ref "PORTDM") (pin "2") (pinfunction "2_2") (pintype "passive"))
    )
    (net (code "30") (name "/RD2") (class "Default")
      (node (ref "IC1") (pin "40") (pinfunction "RD2/CPS10/P2B_40") (pintype "bidirectional"))
      (node (ref "PD") (pin "3") (pinfunction "KL_3") (pintype "passive"))
      (node (ref "PORTDH") (pin "3") (pinfunction "3_3") (pintype "passive"))
      (node (ref "PORTDM") (pin "3") (pinfunction "3_3") (pintype "passive"))
    )
    (net (code "31") (name "/RD3") (class "Default")
      (node (ref "IC1") (pin "41") (pinfunction "RD3/CPS11/P2C/SEG16_41") (pintype "bidirectional"))
      (node (ref "PD") (pin "4") (pinfunction "KL_4") (pintype "passive"))
      (node (ref "PORTDH") (pin "4") (pinfunction "4_4") (pintype "passive"))
      (node (ref "PORTDM") (pin "4") (pinfunction "4_4") (pintype "passive"))
    )
    (net (code "32") (name "/RD4") (class "Default")
      (node (ref "IC1") (pin "2") (pinfunction "SEG17/P2D/CPS12/RD4_2") (pintype "bidirectional"))
      (node (ref "PD") (pin "5") (pinfunction "KL_5") (pintype "passive"))
      (node (ref "PORTDH") (pin "5") (pinfunction "5_5") (pintype "passive"))
      (node (ref "PORTDM") (pin "5") (pinfunction "5_5") (pintype "passive"))
    )
    (net (code "33") (name "/RD5") (class "Default")
      (node (ref "IC1") (pin "3") (pinfunction "SEG18/P1B/CPS13/RD5_3") (pintype "bidirectional"))
      (node (ref "PD") (pin "6") (pinfunction "KL_6") (pintype "passive"))
      (node (ref "PORTDH") (pin "6") (pinfunction "6_6") (pintype "passive"))
      (node (ref "PORTDM") (pin "6") (pinfunction "6_6") (pintype "passive"))
    )
    (net (code "34") (name "/RD6") (class "Default")
      (node (ref "IC1") (pin "4") (pinfunction "SEG19/P1C/CPS14/RD6_4") (pintype "bidirectional"))
      (node (ref "PD") (pin "7") (pinfunction "KL_7") (pintype "passive"))
      (node (ref "PORTDH") (pin "7") (pinfunction "7_7") (pintype "passive"))
      (node (ref "PORTDM") (pin "7") (pinfunction "7_7") (pintype "passive"))
    )
    (net (code "35") (name "/RD7") (class "Default")
      (node (ref "IC1") (pin "5") (pinfunction "SEG20/P1D/CPS15/RD7_5") (pintype "bidirectional"))
      (node (ref "PD") (pin "8") (pinfunction "KL_8") (pintype "passive"))
      (node (ref "PORTDH") (pin "8") (pinfunction "8_8") (pintype "passive"))
      (node (ref "PORTDM") (pin "8") (pinfunction "8_8") (pintype "passive"))
    )
    (net (code "36") (name "/RE0") (class "Default")
      (node (ref "IC1") (pin "25") (pinfunction "RE0/AN5/CCP3/P3A/SEG21_25") (pintype "bidirectional"))
      (node (ref "PORTEH") (pin "1") (pinfunction "1_1") (pintype "passive"))
      (node (ref "PORTEM") (pin "1") (pinfunction "1_1") (pintype "passive"))
    )
    (net (code "37") (name "/RE1") (class "Default")
      (node (ref "IC1") (pin "26") (pinfunction "RE1/AN6/P3B/SEG22_26") (pintype "bidirectional"))
      (node (ref "PORTEH") (pin "2") (pinfunction "2_2") (pintype "passive"))
      (node (ref "PORTEM") (pin "2") (pinfunction "2_2") (pintype "passive"))
    )
    (net (code "38") (name "/RE2") (class "Default")
      (node (ref "IC1") (pin "27") (pinfunction "RE2/AN7/CCP5/SEG23_27") (pintype "bidirectional"))
      (node (ref "PORTEH") (pin "3") (pinfunction "3_3") (pintype "passive"))
      (node (ref "PORTEM") (pin "3") (pinfunction "3_3") (pintype "passive"))
    )
    (net (code "39") (name "/RST") (class "Default")
      (node (ref "SOC_UART") (pin "1") (pinfunction "1_1") (pintype "passive"))
    )
    (net (code "40") (name "/VEXT") (class "Default")
      (node (ref "C6") (pin "P") (pinfunction "P_P") (pintype "bidirectional"))
      (node (ref "IC2") (pin "3") (pinfunction "VO_3") (pintype "passive"))
      (node (ref "PWR_SLIDE") (pin "3") (pinfunction "3_3") (pintype "passive"))
      (node (ref "PWR_SLIDE") (pin "6") (pinfunction "6_6") (pintype "passive"))
    )
    (net (code "41") (name "/VUSB") (class "Default")
      (node (ref "PWR_SLIDE") (pin "1") (pinfunction "1_1") (pintype "passive"))
      (node (ref "PWR_SLIDE") (pin "4") (pinfunction "4_4") (pintype "passive"))
      (node (ref "USB") (pin "1") (pinfunction "1_1") (pintype "passive"))
    )
    (net (code "42") (name "GND") (class "Default")
      (node (ref "C1") (pin "2") (pinfunction "2_2") (pintype "passive"))
      (node (ref "C2") (pin "2") (pinfunction "2_2") (pintype "passive"))
      (node (ref "C3") (pin "N") (pinfunction "N_N") (pintype "bidirectional"))
      (node (ref "C4") (pin "N") (pinfunction "N_N") (pintype "bidirectional"))
      (node (ref "C5") (pin "N") (pinfunction "N_N") (pintype "bidirectional"))
      (node (ref "C6") (pin "N") (pinfunction "N_N") (pintype "bidirectional"))
      (node (ref "IC1") (pin "29") (pinfunction "VSS_29") (pintype "power_in"))
      (node (ref "IC1") (pin "6") (pinfunction "VSS_6") (pintype "power_in"))
      (node (ref "IC2") (pin "2") (pinfunction "GND_2") (pintype "passive"))
      (node (ref "J1") (pin "2") (pinfunction "2_2") (pintype "passive"))
      (node (ref "J1") (pin "3") (pinfunction "3_3") (pintype "passive"))
      (node (ref "JP_3V3") (pin "10") (pinfunction "10_10") (pintype "passive"))
      (node (ref "JP_3V3") (pin "12") (pinfunction "12_12") (pintype "passive"))
      (node (ref "JP_3V3") (pin "14") (pinfunction "14_14") (pintype "passive"))
      (node (ref "JP_3V3") (pin "16") (pinfunction "16_16") (pintype "passive"))
      (node (ref "JP_3V3") (pin "18") (pinfunction "18_18") (pintype "passive"))
      (node (ref "JP_3V3") (pin "2") (pinfunction "2_2") (pintype "passive"))
      (node (ref "JP_3V3") (pin "20") (pinfunction "20_20") (pintype "passive"))
      (node (ref "JP_3V3") (pin "4") (pinfunction "4_4") (pintype "passive"))
      (node (ref "JP_3V3") (pin "6") (pinfunction "6_6") (pintype "passive"))
      (node (ref "JP_3V3") (pin "8") (pinfunction "8_8") (pintype "passive"))
      (node (ref "JP_5V5") (pin "10") (pinfunction "10_10") (pintype "passive"))
      (node (ref "JP_5V5") (pin "12") (pinfunction "12_12") (pintype "passive"))
      (node (ref "JP_5V5") (pin "14") (pinfunction "14_14") (pintype "passive"))
      (node (ref "JP_5V5") (pin "16") (pinfunction "16_16") (pintype "passive"))
      (node (ref "JP_5V5") (pin "18") (pinfunction "18_18") (pintype "passive"))
      (node (ref "JP_5V5") (pin "2") (pinfunction "2_2") (pintype "passive"))
      (node (ref "JP_5V5") (pin "20") (pinfunction "20_20") (pintype "passive"))
      (node (ref "JP_5V5") (pin "4") (pinfunction "4_4") (pintype "passive"))
      (node (ref "JP_5V5") (pin "6") (pinfunction "6_6") (pintype "passive"))
      (node (ref "JP_5V5") (pin "8") (pinfunction "8_8") (pintype "passive"))
      (node (ref "PA") (pin "9") (pinfunction "KL_9") (pintype "passive"))
      (node (ref "PB") (pin "9") (pinfunction "KL_9") (pintype "passive"))
      (node (ref "PC") (pin "9") (pinfunction "KL_9") (pintype "passive"))
      (node (ref "PD") (pin "9") (pinfunction "KL_9") (pintype "passive"))
      (node (ref "PICKIT") (pin "3") (pinfunction "3_3") (pintype "passive"))
      (node (ref "R10") (pin "1") (pinfunction "1_1") (pintype "passive"))
      (node (ref "R11") (pin "1") (pinfunction "1_1") (pintype "passive"))
      (node (ref "R12") (pin "1") (pinfunction "1_1") (pintype "passive"))
      (node (ref "R13") (pin "1") (pinfunction "1_1") (pintype "passive"))
      (node (ref "R14") (pin "1") (pinfunction "1_1") (pintype "passive"))
      (node (ref "R15") (pin "1") (pinfunction "1_1") (pintype "passive"))
      (node (ref "R16") (pin "1") (pinfunction "1_1") (pintype "passive"))
      (node (ref "R17") (pin "1") (pinfunction "1_1") (pintype "passive"))
      (node (ref "R19") (pin "3") (pinfunction "CW_3") (pintype "passive"))
      (node (ref "R2") (pin "1") (pinfunction "1_1") (pintype "passive"))
      (node (ref "R20") (pin "3") (pinfunction "CW_3") (pintype "passive"))
      (node (ref "R21") (pin "3") (pinfunction "CW_3") (pintype "passive"))
      (node (ref "R3") (pin "1") (pinfunction "1_1") (pintype "passive"))
      (node (ref "R4") (pin "1") (pinfunction "1_1") (pintype "passive"))
      (node (ref "R5") (pin "1") (pinfunction "1_1") (pintype "passive"))
      (node (ref "R6") (pin "1") (pinfunction "1_1") (pintype "passive"))
      (node (ref "R7") (pin "1") (pinfunction "1_1") (pintype "passive"))
      (node (ref "R8") (pin "1") (pinfunction "1_1") (pintype "passive"))
      (node (ref "R9") (pin "1") (pinfunction "1_1") (pintype "passive"))
      (node (ref "S1") (pin "3") (pinfunction "3_3") (pintype "passive"))
      (node (ref "S1") (pin "6") (pinfunction "6_6") (pintype "passive"))
      (node (ref "S3") (pin "3") (pinfunction "3_3") (pintype "passive"))
      (node (ref "S3") (pin "6") (pinfunction "6_6") (pintype "passive"))
      (node (ref "S4") (pin "3") (pinfunction "3_3") (pintype "passive"))
      (node (ref "S4") (pin "6") (pinfunction "6_6") (pintype "passive"))
      (node (ref "S5") (pin "3") (pinfunction "3_3") (pintype "passive"))
      (node (ref "S5") (pin "6") (pinfunction "6_6") (pintype "passive"))
      (node (ref "S6") (pin "3") (pinfunction "3_3") (pintype "passive"))
      (node (ref "S6") (pin "6") (pinfunction "6_6") (pintype "passive"))
      (node (ref "S7") (pin "3") (pinfunction "3_3") (pintype "passive"))
      (node (ref "S7") (pin "6") (pinfunction "6_6") (pintype "passive"))
      (node (ref "S8") (pin "3") (pinfunction "3_3") (pintype "passive"))
      (node (ref "S8") (pin "6") (pinfunction "6_6") (pintype "passive"))
      (node (ref "S9") (pin "3") (pinfunction "3_3") (pintype "passive"))
      (node (ref "S9") (pin "6") (pinfunction "6_6") (pintype "passive"))
      (node (ref "SOC_UART") (pin "4") (pinfunction "4_4") (pintype "passive"))
      (node (ref "SW1") (pin "1") (pinfunction "1_1") (pintype "passive"))
      (node (ref "SW1") (pin "2") (pinfunction "2_2") (pintype "passive"))
      (node (ref "U$3") (pin "1") (pinfunction "GND_1") (pintype "bidirectional"))
      (node (ref "USB") (pin "4") (pinfunction "4_4") (pintype "passive"))
      (node (ref "X1") (pin "2") (pinfunction "KL_2") (pintype "passive"))
    )
    (net (code "43") (name "Net-(BTN_A-Pad1)") (class "Default")
      (node (ref "BTN_A") (pin "1") (pinfunction "1_1") (pintype "passive"))
      (node (ref "R10") (pin "2") (pinfunction "2_2") (pintype "passive"))
      (node (ref "S10") (pin "1") (pinfunction "1_1") (pintype "passive"))
    )
    (net (code "44") (name "Net-(BTN_A-Pad2)") (class "Default")
      (node (ref "BTN_A") (pin "2") (pinfunction "2_2") (pintype "passive"))
      (node (ref "R11") (pin "2") (pinfunction "2_2") (pintype "passive"))
      (node (ref "S11") (pin "1") (pinfunction "1_1") (pintype "passive"))
    )
    (net (code "45") (name "Net-(BTN_A-Pad3)") (class "Default")
      (node (ref "BTN_A") (pin "3") (pinfunction "3_3") (pintype "passive"))
      (node (ref "R12") (pin "2") (pinfunction "2_2") (pintype "passive"))
      (node (ref "S12") (pin "1") (pinfunction "1_1") (pintype "passive"))
    )
    (net (code "46") (name "Net-(BTN_A-Pad4)") (class "Default")
      (node (ref "BTN_A") (pin "4") (pinfunction "4_4") (pintype "passive"))
      (node (ref "R13") (pin "2") (pinfunction "2_2") (pintype "passive"))
      (node (ref "S13") (pin "1") (pinfunction "1_1") (pintype "passive"))
    )
    (net (code "47") (name "Net-(BTN_B-Pad1)") (class "Default")
      (node (ref "BTN_B") (pin "1") (pinfunction "1_1") (pintype "passive"))
      (node (ref "R17") (pin "2") (pinfunction "2_2") (pintype "passive"))
      (node (ref "S17") (pin "1") (pinfunction "1_1") (pintype "passive"))
    )
    (net (code "48") (name "Net-(BTN_B-Pad2)") (class "Default")
      (node (ref "BTN_B") (pin "2") (pinfunction "2_2") (pintype "passive"))
      (node (ref "R16") (pin "2") (pinfunction "2_2") (pintype "passive"))
      (node (ref "S16") (pin "1") (pinfunction "1_1") (pintype "passive"))
    )
    (net (code "49") (name "Net-(BTN_B-Pad3)") (class "Default")
      (node (ref "BTN_B") (pin "3") (pinfunction "3_3") (pintype "passive"))
      (node (ref "R15") (pin "2") (pinfunction "2_2") (pintype "passive"))
      (node (ref "S15") (pin "1") (pinfunction "1_1") (pintype "passive"))
    )
    (net (code "50") (name "Net-(BTN_B-Pad4)") (class "Default")
      (node (ref "BTN_B") (pin "4") (pinfunction "4_4") (pintype "passive"))
      (node (ref "R14") (pin "2") (pinfunction "2_2") (pintype "passive"))
      (node (ref "S14") (pin "1") (pinfunction "1_1") (pintype "passive"))
    )
    (net (code "51") (name "Net-(IC2-VI)") (class "Default")
      (node (ref "C5") (pin "P") (pinfunction "P_P") (pintype "bidirectional"))
      (node (ref "IC2") (pin "1") (pinfunction "VI_1") (pintype "input"))
      (node (ref "J1") (pin "1") (pinfunction "1_1") (pintype "passive"))
      (node (ref "X1") (pin "1") (pinfunction "KL_1") (pintype "passive"))
    )
    (net (code "52") (name "Net-(JP_SLIDES_DOWN-Pad1)") (class "Default")
      (node (ref "JP_SLIDES_DOWN") (pin "1") (pinfunction "1_1") (pintype "passive"))
      (node (ref "R26") (pin "1") (pinfunction "1_1") (pintype "passive"))
    )
    (net (code "53") (name "Net-(JP_SLIDES_DOWN-Pad2)") (class "Default")
      (node (ref "JP_SLIDES_DOWN") (pin "2") (pinfunction "2_2") (pintype "passive"))
      (node (ref "R25") (pin "1") (pinfunction "1_1") (pintype "passive"))
    )
    (net (code "54") (name "Net-(JP_SLIDES_DOWN-Pad3)") (class "Default")
      (node (ref "JP_SLIDES_DOWN") (pin "3") (pinfunction "3_3") (pintype "passive"))
      (node (ref "R24") (pin "1") (pinfunction "1_1") (pintype "passive"))
    )
    (net (code "55") (name "Net-(JP_SLIDES_DOWN-Pad4)") (class "Default")
      (node (ref "JP_SLIDES_DOWN") (pin "4") (pinfunction "4_4") (pintype "passive"))
      (node (ref "R23") (pin "1") (pinfunction "1_1") (pintype "passive"))
    )
    (net (code "56") (name "Net-(JP_SLIDES_UP-Pad1)") (class "Default")
      (node (ref "JP_SLIDES_UP") (pin "1") (pinfunction "1_1") (pintype "passive"))
      (node (ref "R27") (pin "1") (pinfunction "1_1") (pintype "passive"))
    )
    (net (code "57") (name "Net-(JP_SLIDES_UP-Pad2)") (class "Default")
      (node (ref "JP_SLIDES_UP") (pin "2") (pinfunction "2_2") (pintype "passive"))
      (node (ref "R28") (pin "1") (pinfunction "1_1") (pintype "passive"))
    )
    (net (code "58") (name "Net-(JP_SLIDES_UP-Pad3)") (class "Default")
      (node (ref "JP_SLIDES_UP") (pin "3") (pinfunction "3_3") (pintype "passive"))
      (node (ref "R29") (pin "1") (pinfunction "1_1") (pintype "passive"))
    )
    (net (code "59") (name "Net-(JP_SLIDES_UP-Pad4)") (class "Default")
      (node (ref "JP_SLIDES_UP") (pin "4") (pinfunction "4_4") (pintype "passive"))
      (node (ref "R30") (pin "1") (pinfunction "1_1") (pintype "passive"))
    )
    (net (code "60") (name "Net-(L1-PadA)") (class "Default")
      (node (ref "L1") (pin "A") (pinfunction "A_A") (pintype "passive"))
      (node (ref "LEDS1") (pin "1") (pinfunction "1_1") (pintype "passive"))
    )
    (net (code "61") (name "Net-(L1-PadC)") (class "Default")
      (node (ref "L1") (pin "C") (pinfunction "C_C") (pintype "passive"))
      (node (ref "R2") (pin "2") (pinfunction "2_2") (pintype "passive"))
    )
    (net (code "62") (name "Net-(L4-PadA)") (class "Default")
      (node (ref "L4") (pin "A") (pinfunction "A_A") (pintype "passive"))
      (node (ref "LEDS1") (pin "4") (pinfunction "4_4") (pintype "passive"))
    )
    (net (code "63") (name "Net-(L4-PadC)") (class "Default")
      (node (ref "L4") (pin "C") (pinfunction "C_C") (pintype "passive"))
      (node (ref "R5") (pin "2") (pinfunction "2_2") (pintype "passive"))
    )
    (net (code "64") (name "Net-(L5-PadA)") (class "Default")
      (node (ref "L5") (pin "A") (pinfunction "A_A") (pintype "passive"))
      (node (ref "LEDS2") (pin "1") (pinfunction "1_1") (pintype "passive"))
    )
    (net (code "65") (name "Net-(L5-PadC)") (class "Default")
      (node (ref "L5") (pin "C") (pinfunction "C_C") (pintype "passive"))
      (node (ref "R6") (pin "2") (pinfunction "2_2") (pintype "passive"))
    )
    (net (code "66") (name "Net-(L8-PadA)") (class "Default")
      (node (ref "L8") (pin "A") (pinfunction "A_A") (pintype "passive"))
      (node (ref "LEDS2") (pin "4") (pinfunction "4_4") (pintype "passive"))
    )
    (net (code "67") (name "Net-(L8-PadC)") (class "Default")
      (node (ref "L8") (pin "C") (pinfunction "C_C") (pintype "passive"))
      (node (ref "R9") (pin "2") (pinfunction "2_2") (pintype "passive"))
    )
    (net (code "68") (name "Net-(LED2-PadA)") (class "Default")
      (node (ref "LED2") (pin "A") (pinfunction "A_A") (pintype "passive"))
      (node (ref "LEDS1") (pin "2") (pinfunction "2_2") (pintype "passive"))
    )
    (net (code "69") (name "Net-(LED2-PadC)") (class "Default")
      (node (ref "LED2") (pin "C") (pinfunction "C_C") (pintype "passive"))
      (node (ref "R3") (pin "2") (pinfunction "2_2") (pintype "passive"))
    )
    (net (code "70") (name "Net-(LED3-PadA)") (class "Default")
      (node (ref "LED3") (pin "A") (pinfunction "A_A") (pintype "passive"))
      (node (ref "LEDS1") (pin "3") (pinfunction "3_3") (pintype "passive"))
    )
    (net (code "71") (name "Net-(LED3-PadC)") (class "Default")
      (node (ref "LED3") (pin "C") (pinfunction "C_C") (pintype "passive"))
      (node (ref "R4") (pin "2") (pinfunction "2_2") (pintype "passive"))
    )
    (net (code "72") (name "Net-(LED6-PadA)") (class "Default")
      (node (ref "LED6") (pin "A") (pinfunction "A_A") (pintype "passive"))
      (node (ref "LEDS2") (pin "2") (pinfunction "2_2") (pintype "passive"))
    )
    (net (code "73") (name "Net-(LED6-PadC)") (class "Default")
      (node (ref "LED6") (pin "C") (pinfunction "C_C") (pintype "passive"))
      (node (ref "R7") (pin "2") (pinfunction "2_2") (pintype "passive"))
    )
    (net (code "74") (name "Net-(LED7-PadA)") (class "Default")
      (node (ref "LED7") (pin "A") (pinfunction "A_A") (pintype "passive"))
      (node (ref "LEDS2") (pin "3") (pinfunction "3_3") (pintype "passive"))
    )
    (net (code "75") (name "Net-(LED7-PadC)") (class "Default")
      (node (ref "LED7") (pin "C") (pinfunction "C_C") (pintype "passive"))
      (node (ref "R8") (pin "2") (pinfunction "2_2") (pintype "passive"))
    )
    (net (code "76") (name "Net-(R19-WIPER)") (class "Default")
      (node (ref "POT") (pin "1") (pinfunction "1_1") (pintype "passive"))
      (node (ref "R19") (pin "2") (pinfunction "WIPER_2") (pintype "passive"))
    )
    (net (code "77") (name "Net-(R20-WIPER)") (class "Default")
      (node (ref "POT") (pin "2") (pinfunction "2_2") (pintype "passive"))
      (node (ref "R20") (pin "2") (pinfunction "WIPER_2") (pintype "passive"))
    )
    (net (code "78") (name "Net-(R21-WIPER)") (class "Default")
      (node (ref "POT") (pin "3") (pinfunction "3_3") (pintype "passive"))
      (node (ref "R21") (pin "2") (pinfunction "WIPER_2") (pintype "passive"))
    )
    (net (code "79") (name "Net-(R23-Pad2)") (class "Default")
      (node (ref "R23") (pin "2") (pinfunction "2_2") (pintype "passive"))
      (node (ref "S1") (pin "2") (pinfunction "2_2") (pintype "passive"))
      (node (ref "S1") (pin "5") (pinfunction "5_5") (pintype "passive"))
    )
    (net (code "80") (name "Net-(R24-Pad2)") (class "Default")
      (node (ref "R24") (pin "2") (pinfunction "2_2") (pintype "passive"))
      (node (ref "S3") (pin "2") (pinfunction "2_2") (pintype "passive"))
      (node (ref "S3") (pin "5") (pinfunction "5_5") (pintype "passive"))
    )
    (net (code "81") (name "Net-(R25-Pad2)") (class "Default")
      (node (ref "R25") (pin "2") (pinfunction "2_2") (pintype "passive"))
      (node (ref "S4") (pin "2") (pinfunction "2_2") (pintype "passive"))
      (node (ref "S4") (pin "5") (pinfunction "5_5") (pintype "passive"))
    )
    (net (code "82") (name "Net-(R26-Pad2)") (class "Default")
      (node (ref "R26") (pin "2") (pinfunction "2_2") (pintype "passive"))
      (node (ref "S5") (pin "2") (pinfunction "2_2") (pintype "passive"))
      (node (ref "S5") (pin "5") (pinfunction "5_5") (pintype "passive"))
    )
    (net (code "83") (name "Net-(R27-Pad2)") (class "Default")
      (node (ref "R27") (pin "2") (pinfunction "2_2") (pintype "passive"))
      (node (ref "S9") (pin "2") (pinfunction "2_2") (pintype "passive"))
      (node (ref "S9") (pin "5") (pinfunction "5_5") (pintype "passive"))
    )
    (net (code "84") (name "Net-(R28-Pad2)") (class "Default")
      (node (ref "R28") (pin "2") (pinfunction "2_2") (pintype "passive"))
      (node (ref "S8") (pin "2") (pinfunction "2_2") (pintype "passive"))
      (node (ref "S8") (pin "5") (pinfunction "5_5") (pintype "passive"))
    )
    (net (code "85") (name "Net-(R29-Pad2)") (class "Default")
      (node (ref "R29") (pin "2") (pinfunction "2_2") (pintype "passive"))
      (node (ref "S7") (pin "2") (pinfunction "2_2") (pintype "passive"))
      (node (ref "S7") (pin "5") (pinfunction "5_5") (pintype "passive"))
    )
    (net (code "86") (name "Net-(R30-Pad2)") (class "Default")
      (node (ref "R30") (pin "2") (pinfunction "2_2") (pintype "passive"))
      (node (ref "S6") (pin "2") (pinfunction "2_2") (pintype "passive"))
      (node (ref "S6") (pin "5") (pinfunction "5_5") (pintype "passive"))
    )
    (net (code "87") (name "VCC") (class "Default")
      (node (ref "C3") (pin "P") (pinfunction "P_P") (pintype "bidirectional"))
      (node (ref "IC1") (pin "28") (pinfunction "VDD_28") (pintype "power_in"))
      (node (ref "IC1") (pin "7") (pinfunction "VDD_7") (pintype "power_in"))
      (node (ref "JP_5V5") (pin "1") (pinfunction "1_1") (pintype "passive"))
      (node (ref "JP_5V5") (pin "11") (pinfunction "11_11") (pintype "passive"))
      (node (ref "JP_5V5") (pin "13") (pinfunction "13_13") (pintype "passive"))
      (node (ref "JP_5V5") (pin "15") (pinfunction "15_15") (pintype "passive"))
      (node (ref "JP_5V5") (pin "17") (pinfunction "17_17") (pintype "passive"))
      (node (ref "JP_5V5") (pin "19") (pinfunction "19_19") (pintype "passive"))
      (node (ref "JP_5V5") (pin "3") (pinfunction "3_3") (pintype "passive"))
      (node (ref "JP_5V5") (pin "5") (pinfunction "5_5") (pintype "passive"))
      (node (ref "JP_5V5") (pin "7") (pinfunction "7_7") (pintype "passive"))
      (node (ref "JP_5V5") (pin "9") (pinfunction "9_9") (pintype "passive"))
      (node (ref "PA") (pin "10") (pinfunction "KL_10") (pintype "passive"))
      (node (ref "PB") (pin "10") (pinfunction "KL_10") (pintype "passive"))
      (node (ref "PC") (pin "10") (pinfunction "KL_10") (pintype "passive"))
      (node (ref "PD") (pin "10") (pinfunction "KL_10") (pintype "passive"))
      (node (ref "PICKIT") (pin "2") (pinfunction "2_2") (pintype "passive"))
      (node (ref "PWR_SLIDE") (pin "2") (pinfunction "2_2") (pintype "passive"))
      (node (ref "PWR_SLIDE") (pin "5") (pinfunction "5_5") (pintype "passive"))
      (node (ref "R1") (pin "2") (pinfunction "2_2") (pintype "passive"))
      (node (ref "R18") (pin "2") (pinfunction "2_2") (pintype "passive"))
      (node (ref "R19") (pin "1") (pinfunction "CCW_1") (pintype "passive"))
      (node (ref "R20") (pin "1") (pinfunction "CCW_1") (pintype "passive"))
      (node (ref "R21") (pin "1") (pinfunction "CCW_1") (pintype "passive"))
      (node (ref "R22") (pin "2") (pinfunction "2_2") (pintype "passive"))
      (node (ref "S1") (pin "1") (pinfunction "1_1") (pintype "passive"))
      (node (ref "S1") (pin "4") (pinfunction "4_4") (pintype "passive"))
      (node (ref "S10") (pin "2") (pinfunction "2_2") (pintype "passive"))
      (node (ref "S11") (pin "2") (pinfunction "2_2") (pintype "passive"))
      (node (ref "S12") (pin "2") (pinfunction "2_2") (pintype "passive"))
      (node (ref "S13") (pin "2") (pinfunction "2_2") (pintype "passive"))
      (node (ref "S14") (pin "2") (pinfunction "2_2") (pintype "passive"))
      (node (ref "S15") (pin "2") (pinfunction "2_2") (pintype "passive"))
      (node (ref "S16") (pin "2") (pinfunction "2_2") (pintype "passive"))
      (node (ref "S17") (pin "2") (pinfunction "2_2") (pintype "passive"))
      (node (ref "S3") (pin "1") (pinfunction "1_1") (pintype "passive"))
      (node (ref "S3") (pin "4") (pinfunction "4_4") (pintype "passive"))
      (node (ref "S4") (pin "1") (pinfunction "1_1") (pintype "passive"))
      (node (ref "S4") (pin "4") (pinfunction "4_4") (pintype "passive"))
      (node (ref "S5") (pin "1") (pinfunction "1_1") (pintype "passive"))
      (node (ref "S5") (pin "4") (pinfunction "4_4") (pintype "passive"))
      (node (ref "S6") (pin "1") (pinfunction "1_1") (pintype "passive"))
      (node (ref "S6") (pin "4") (pinfunction "4_4") (pintype "passive"))
      (node (ref "S7") (pin "1") (pinfunction "1_1") (pintype "passive"))
      (node (ref "S7") (pin "4") (pinfunction "4_4") (pintype "passive"))
      (node (ref "S8") (pin "1") (pinfunction "1_1") (pintype "passive"))
      (node (ref "S8") (pin "4") (pinfunction "4_4") (pintype "passive"))
      (node (ref "S9") (pin "1") (pinfunction "1_1") (pintype "passive"))
      (node (ref "S9") (pin "4") (pinfunction "4_4") (pintype "passive"))
      (node (ref "SOC_UART") (pin "5") (pinfunction "5_5") (pintype "passive"))
      (node (ref "U$3") (pin "3") (pinfunction "IN_3") (pintype "bidirectional"))
    )
    (net (code "88") (name "unconnected-(IC1-NC-Pad12)") (class "Default")
      (node (ref "IC1") (pin "12") (pinfunction "NC_12") (pintype "no_connect"))
    )
    (net (code "89") (name "unconnected-(IC1-NC-Pad13)") (class "Default")
      (node (ref "IC1") (pin "13") (pinfunction "NC_13") (pintype "no_connect"))
    )
    (net (code "90") (name "unconnected-(IC1-NC-Pad33)") (class "Default")
      (node (ref "IC1") (pin "33") (pinfunction "NC_33") (pintype "no_connect"))
    )
    (net (code "91") (name "unconnected-(IC1-NC-Pad34)") (class "Default")
      (node (ref "IC1") (pin "34") (pinfunction "NC_34") (pintype "no_connect"))
    )
    (net (code "92") (name "unconnected-(USB-Pad2)") (class "Default")
      (node (ref "USB") (pin "2") (pinfunction "2_2") (pintype "passive"))
    )
    (net (code "93") (name "unconnected-(USB-Pad3)") (class "Default")
      (node (ref "USB") (pin "3") (pinfunction "3_3") (pintype "passive"))
    )
  )
)
